# LPCB234_-_POWER_INPUT.net
KiCad netlist of a schematic drawn in Altium Designer
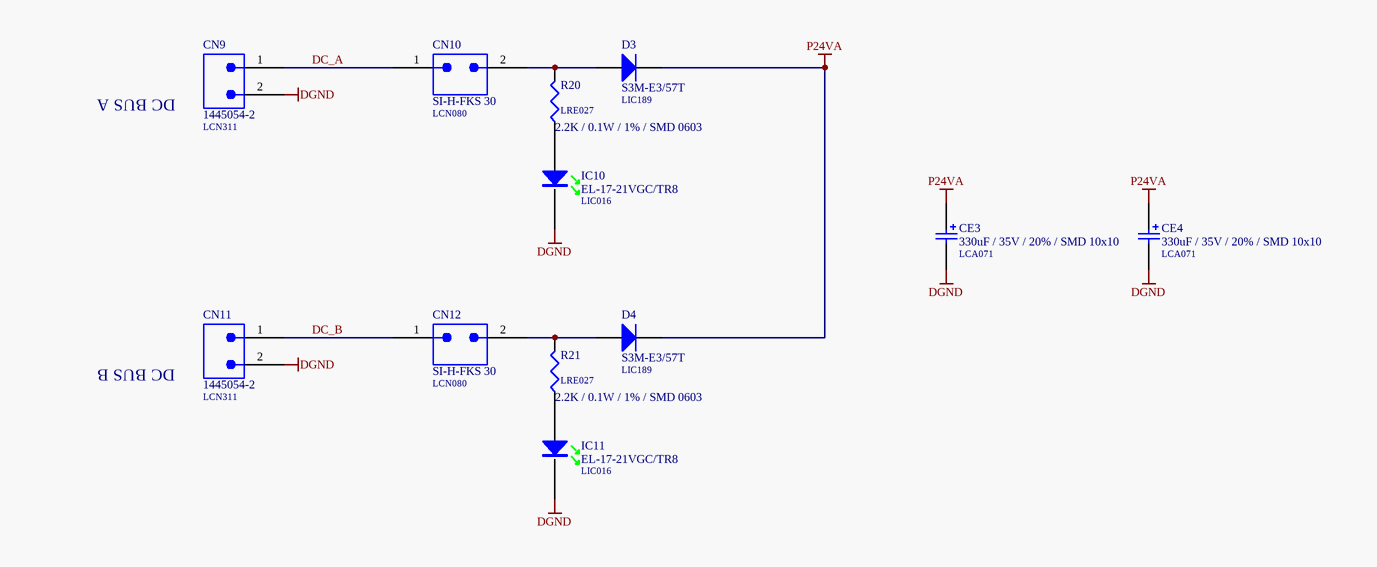
[diagram p0: LPCB234 - POWER INPUT.SchDoc]

(export (version "E")
  (design (tool "Eeschema 10.0.6"))
  (components
    (comp (ref "CE3")
      (value "330uF / 35V / 20% / SMD 10x10")
      (footprint "LFP041__NICHICON_WT_10X10")
      (description "Capacitor, Aluminum Electrolytic, 330uF, 35V, 20%, SMD (10mm x 10mm) [LCA071]")
      (fields (field (name "LDL_NUMBER") "LCA071"))
      (libsource (lib "LDL_Capacitors") (part "330uF / 35V / 20% / SMD 10x10"))
    )
    (comp (ref "CE4")
      (value "330uF / 35V / 20% / SMD 10x10")
      (footprint "LFP041__NICHICON_WT_10X10")
      (description "Capacitor, Aluminum Electrolytic, 330uF, 35V, 20%, SMD (10mm x 10mm) [LCA071]")
      (fields (field (name "LDL_NUMBER") "LCA071"))
      (libsource (lib "LDL_Capacitors") (part "330uF / 35V / 20% / SMD 10x10"))
    )
    (comp (ref "CN9")
      (value "1445054-2")
      (footprint "1445054-2")
      (description "Connector, MATE-N-LOK, Header, 2 Way, PTH")
      (fields (field (name "LDL_NUMBER") "LCN311"))
      (libsource (lib "LDL_Connectors") (part "1445054-2"))
    )
    (comp (ref "CN10")
      (value "SI-H-FKS 30")
      (footprint "SI-H-FKS-30")
      (description "Connector, Blade Fuse Holder, 5mm Terminals, 30A Max, PTH")
      (fields (field (name "LDL_NUMBER") "LCN080"))
      (libsource (lib "LDL_Connectors") (part "SI-H-FKS 30"))
    )
    (comp (ref "CN11")
      (value "1445054-2")
      (footprint "1445054-2")
      (description "Connector, MATE-N-LOK, Header, 2 Way, PTH")
      (fields (field (name "LDL_NUMBER") "LCN311"))
      (libsource (lib "LDL_Connectors") (part "1445054-2"))
    )
    (comp (ref "CN12")
      (value "SI-H-FKS 30")
      (footprint "SI-H-FKS-30")
      (description "Connector, Blade Fuse Holder, 5mm Terminals, 30A Max, PTH")
      (fields (field (name "LDL_NUMBER") "LCN080"))
      (libsource (lib "LDL_Connectors") (part "SI-H-FKS 30"))
    )
    (comp (ref "D3")
      (value "S3M-E3/57T")
      (footprint "LFP040__DO-214AB")
      (description "Diode, General Purpose Rectifier, 3A, 200V, SMD DO-214AB [LIC189]")
      (fields (field (name "LDL_NUMBER") "LIC189"))
      (libsource (lib "LDL_Semiconductors") (part "S3M-E3/57T"))
    )
    (comp (ref "D4")
      (value "S3M-E3/57T")
      (footprint "LFP040__DO-214AB")
      (description "Diode, General Purpose Rectifier, 3A, 200V, SMD DO-214AB [LIC189]")
      (fields (field (name "LDL_NUMBER") "LIC189"))
      (libsource (lib "LDL_Semiconductors") (part "S3M-E3/57T"))
    )
    (comp (ref "IC10")
      (value "EL-17-21VGC/TR8")
      (footprint "CR2012-0805-LED")
      (description "LED, SMD, 0805 Green [LIC016]")
      (fields (field (name "LDL_NUMBER") "LIC016"))
      (libsource (lib "LDL_Semiconductors") (part "EL-17-21VGC/TR8"))
    )
    (comp (ref "IC11")
      (value "EL-17-21VGC/TR8")
      (footprint "CR2012-0805-LED")
      (description "LED, SMD, 0805 Green [LIC016]")
      (fields (field (name "LDL_NUMBER") "LIC016"))
      (libsource (lib "LDL_Semiconductors") (part "EL-17-21VGC/TR8"))
    )
    (comp (ref "R20")
      (value "2.2K / 0.1W / 1% / SMD 0603")
      (footprint "LFP020__CR1608-0603-IPC7351_B")
      (description "Resistor, Ceramic Chip, 2.2K, 0.1W, 1%, SMD 0603 [LRE027]")
      (fields (field (name "LDL_NUMBER") "LRE027"))
      (libsource (lib "LDL_Resistors") (part "2.2K / 0.1W / 1% / SMD 0603"))
    )
    (comp (ref "R21")
      (value "2.2K / 0.1W / 1% / SMD 0603")
      (footprint "LFP020__CR1608-0603-IPC7351_B")
      (description "Resistor, Ceramic Chip, 2.2K, 0.1W, 1%, SMD 0603 [LRE027]")
      (fields (field (name "LDL_NUMBER") "LRE027"))
      (libsource (lib "LDL_Resistors") (part "2.2K / 0.1W / 1% / SMD 0603"))
    )
  )
  (nets
    (net (code "1") (name "/DC_A") (class "Default")
      (node (ref "CN10") (pin "1") (pinfunction "1_1") (pintype "passive"))
      (node (ref "CN9") (pin "1") (pinfunction "1_1") (pintype "passive"))
    )
    (net (code "2") (name "/DC_B") (class "Default")
      (node (ref "CN11") (pin "1") (pinfunction "1_1") (pintype "passive"))
      (node (ref "CN12") (pin "1") (pinfunction "1_1") (pintype "passive"))
    )
    (net (code "3") (name "DGND") (class "Default")
      (node (ref "CE3") (pin "2") (pinfunction "2_2") (pintype "passive"))
      (node (ref "CE4") (pin "2") (pinfunction "2_2") (pintype "passive"))
      (node (ref "CN11") (pin "2") (pinfunction "2_2") (pintype "passive"))
      (node (ref "CN9") (pin "2") (pinfunction "2_2") (pintype "passive"))
      (node (ref "IC10") (pin "K") (pintype "passive"))
      (node (ref "IC11") (pin "K") (pintype "passive"))
    )
    (net (code "4") (name "Net-(D3-A)") (class "Default")
      (node (ref "CN10") (pin "2") (pinfunction "2_2") (pintype "passive"))
      (node (ref "D3") (pin "2") (pinfunction "A_2") (pintype "passive"))
      (node (ref "R20") (pin "2") (pintype "passive"))
    )
    (net (code "5") (name "Net-(D4-A)") (class "Default")
      (node (ref "CN12") (pin "2") (pinfunction "2_2") (pintype "passive"))
      (node (ref "D4") (pin "2") (pinfunction "A_2") (pintype "passive"))
      (node (ref "R21") (pin "2") (pintype "passive"))
    )
    (net (code "6") (name "Net-(IC10-PadA)") (class "Default")
      (node (ref "IC10") (pin "A") (pintype "passive"))
      (node (ref "R20") (pin "1") (pintype "passive"))
    )
    (net (code "7") (name "Net-(IC11-PadA)") (class "Default")
      (node (ref "IC11") (pin "A") (pintype "passive"))
      (node (ref "R21") (pin "1") (pintype "passive"))
    )
    (net (code "8") (name "P24VA") (class "Default")
      (node (ref "CE3") (pin "1") (pinfunction "1_1") (pintype "passive"))
      (node (ref "CE4") (pin "1") (pinfunction "1_1") (pintype "passive"))
      (node (ref "D3") (pin "1") (pinfunction "K_1") (pintype "passive"))
      (node (ref "D4") (pin "1") (pinfunction "K_1") (pintype "passive"))
    )
  )
)
